# ElectroII.net
KiCad netlist of a schematic drawn in EAGLE
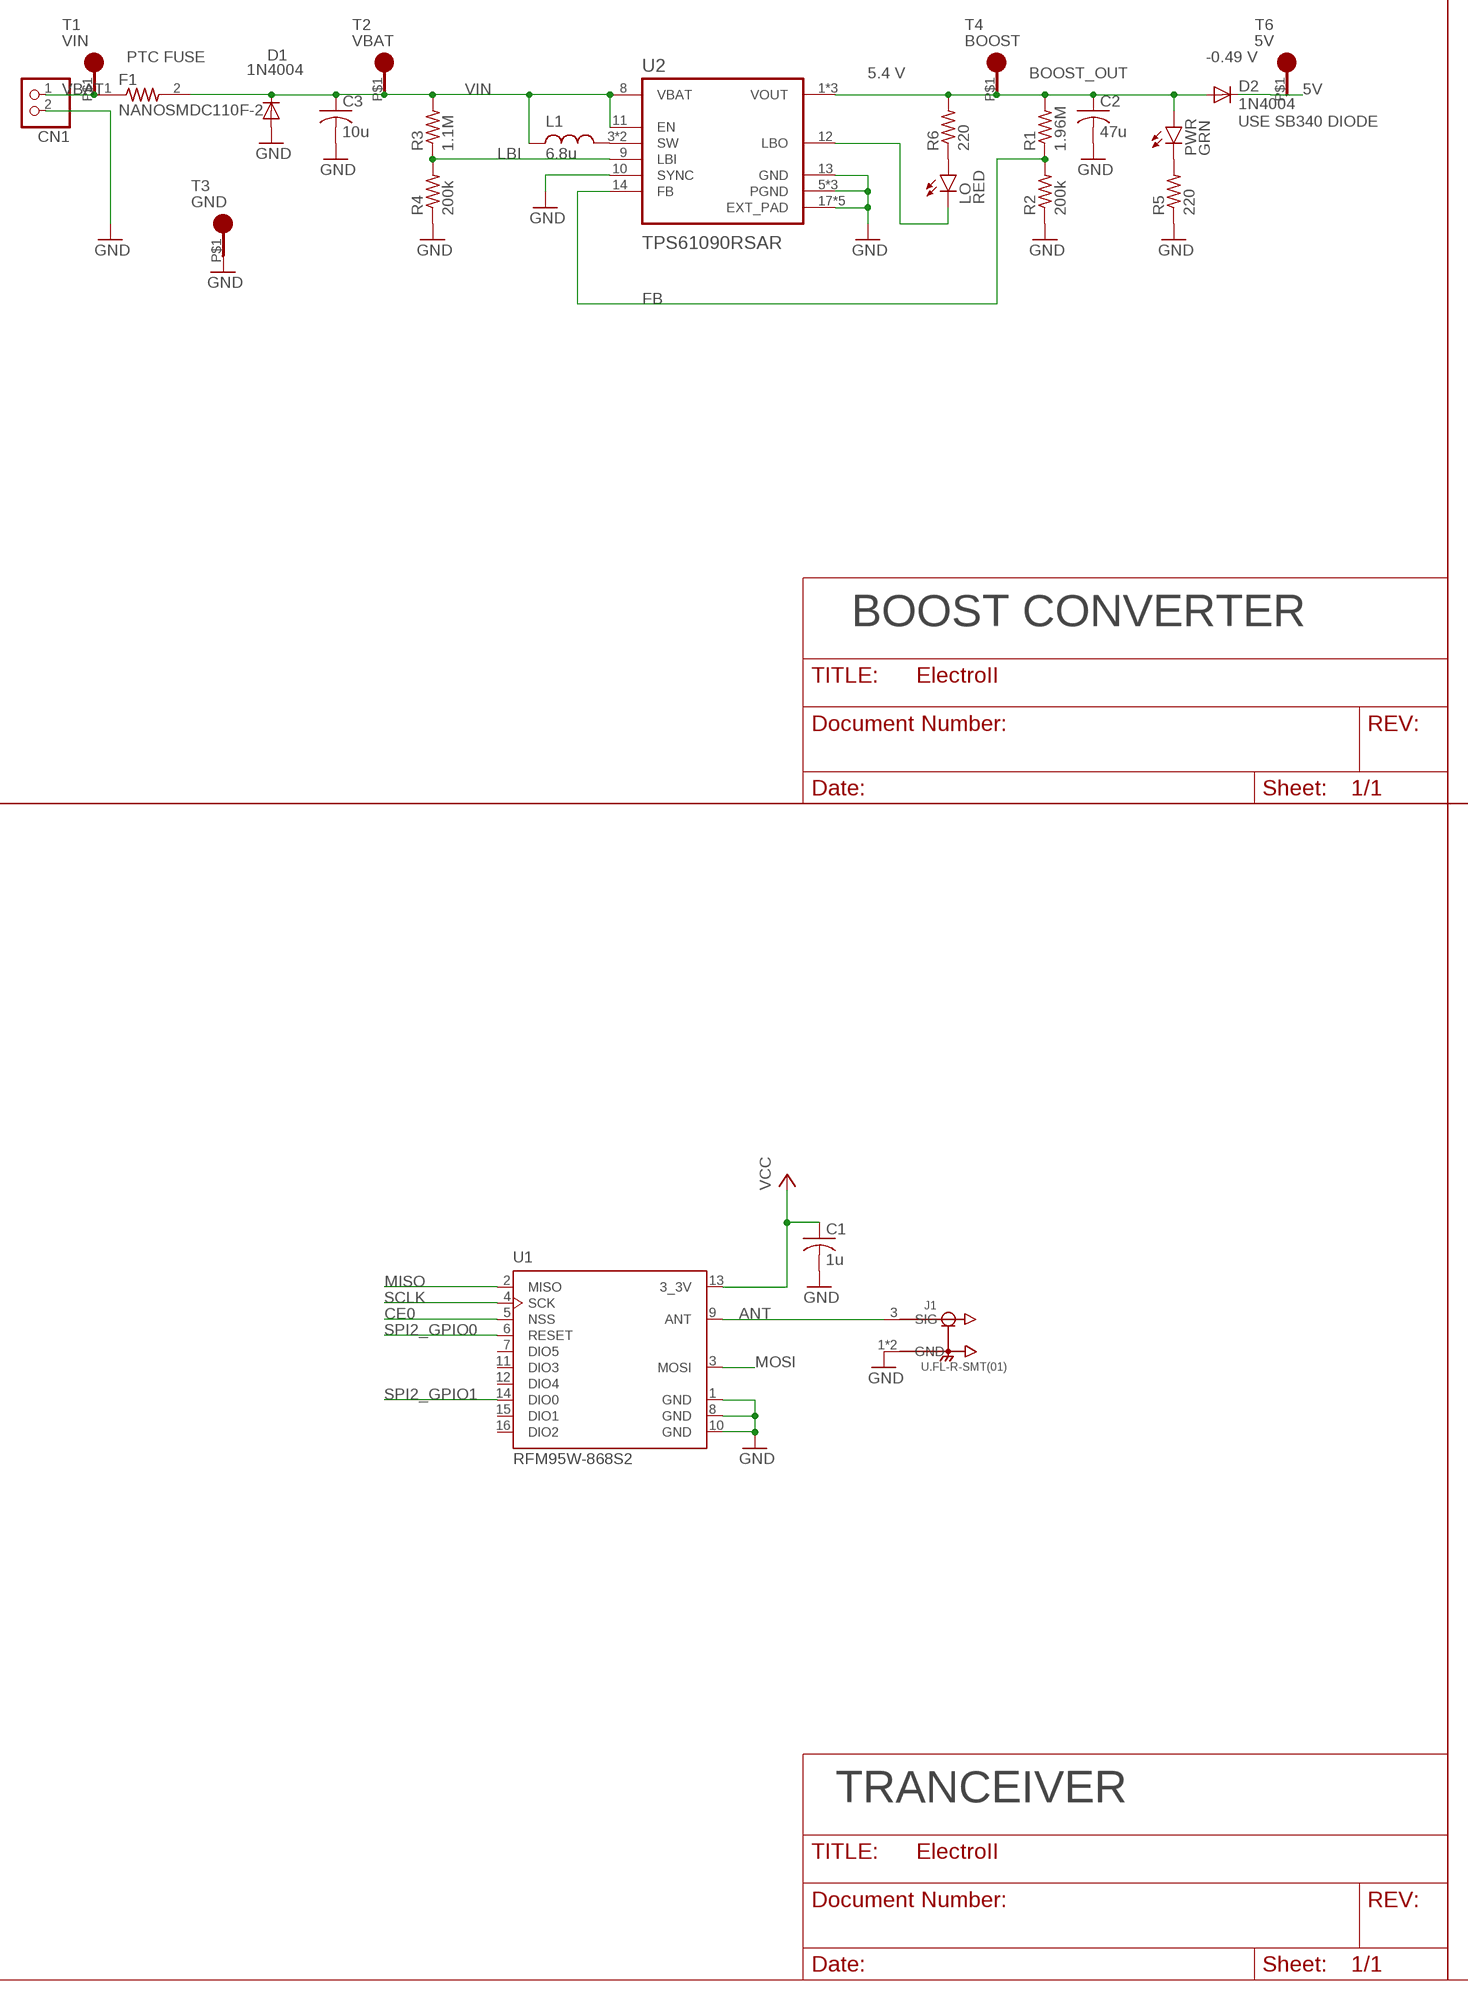
[diagram p0: schematic, sheet 1, part 1 of 2]
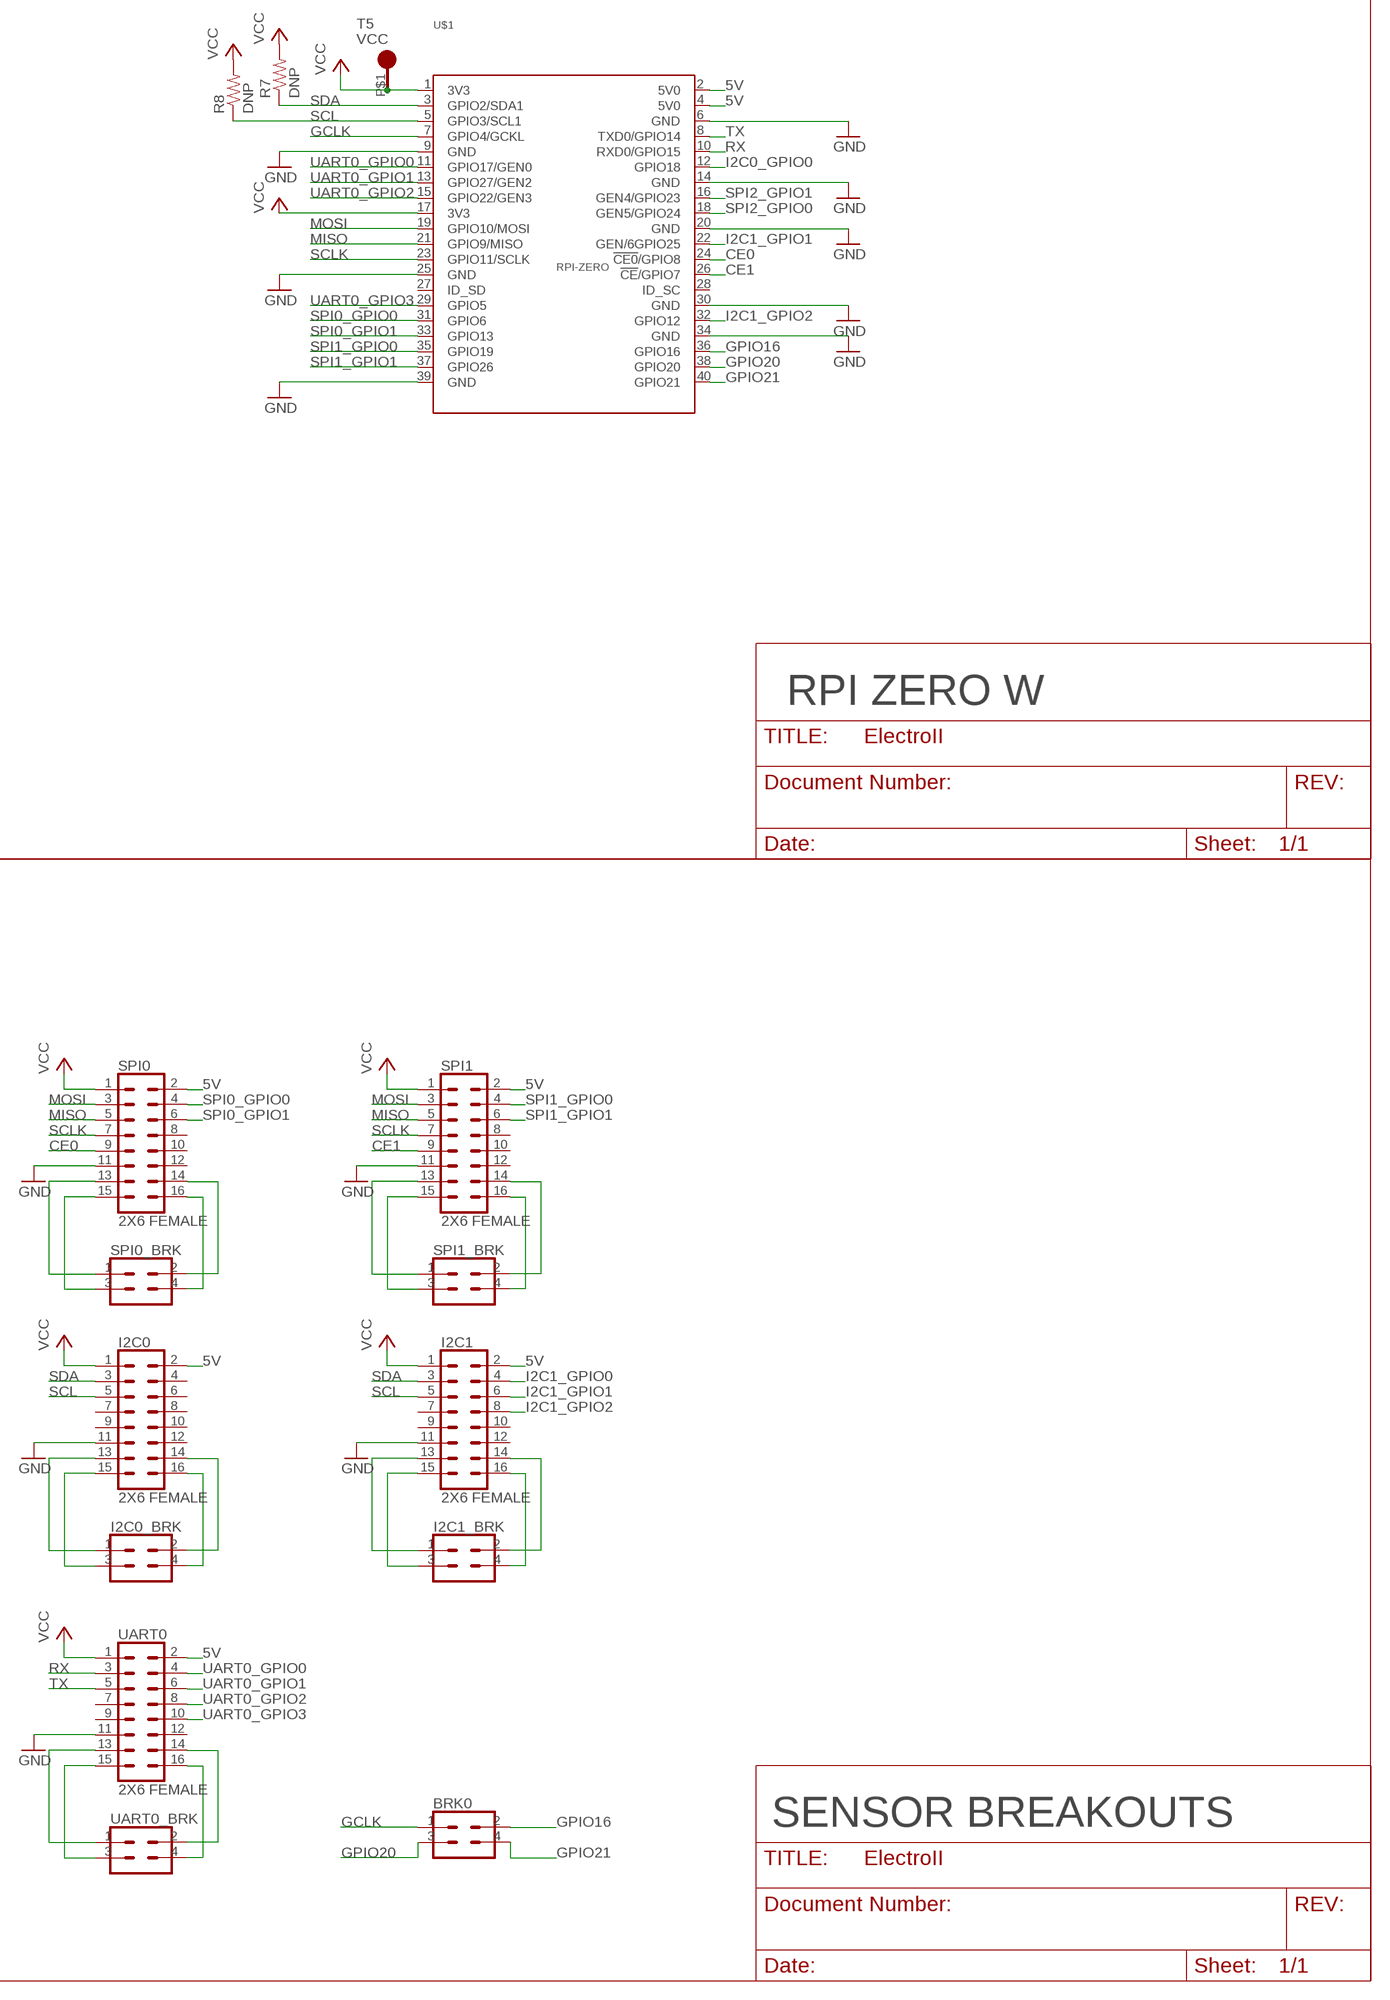
[diagram p1: schematic, sheet 1, part 2 of 2]

(export (version "E")
  (design (tool "Eeschema 10.0.6"))
  (components
    (comp (ref "BRK0")
      (value "SENSOR_PIN_BREAKOUT")
      (footprint "eagle-import:2X2")
      (libsource (lib "eagle-import") (part "SENSOR_PIN_BREAKOUT"))
    )
    (comp (ref "C1")
      (value "1u")
      (footprint "eagle-import:C1206")
      (libsource (lib "eagle-import") (part "C-ALL_PACKAGESC1206"))
    )
    (comp (ref "C2")
      (value "47u")
      (footprint "eagle-import:C1206")
      (libsource (lib "eagle-import") (part "C-ALL_PACKAGESC1206"))
    )
    (comp (ref "C3")
      (value "10u")
      (footprint "eagle-import:C1206")
      (libsource (lib "eagle-import") (part "C-ALL_PACKAGESC1206"))
    )
    (comp (ref "CN1")
      (value "JST_2PIN-SMT-RA")
      (footprint "eagle-import:JST-PH-2-SMT-RA")
      (libsource (lib "eagle-import") (part "JST_2PIN-SMT-RA"))
    )
    (comp (ref "D1")
      (value "1N4004")
      (footprint "eagle-import:DO41-10")
      (libsource (lib "eagle-import") (part "1N4004"))
    )
    (comp (ref "D2")
      (value "1N4004")
      (footprint "eagle-import:DO41-10")
      (libsource (lib "eagle-import") (part "1N4004"))
    )
    (comp (ref "F1")
      (value "NANOSMDC110F-2")
      (footprint "eagle-import:RESC3115X65N")
      (fields
        (field (name "DIGI-KEY_PART_NUMBER") "NANOSMDC110F-2CT-ND")
        (field (name "MF") "Littelfuse Inc.")
      )
      (libsource (lib "eagle-import") (part "NANOSMDC110F-2"))
    )
    (comp (ref "I2C0")
      (value "2X6 FEMALE")
      (footprint "eagle-import:2X7")
      (libsource (lib "eagle-import") (part "SENSOR_BREAKOUTPTH_FEMALE"))
    )
    (comp (ref "I2C0_BRK")
      (value "SENSOR_PIN_BREAKOUT")
      (footprint "eagle-import:2X2")
      (libsource (lib "eagle-import") (part "SENSOR_PIN_BREAKOUT"))
    )
    (comp (ref "I2C1")
      (value "2X6 FEMALE")
      (footprint "eagle-import:2X7")
      (libsource (lib "eagle-import") (part "SENSOR_BREAKOUTPTH_FEMALE"))
    )
    (comp (ref "I2C1_BRK")
      (value "SENSOR_PIN_BREAKOUT")
      (footprint "eagle-import:2X2")
      (libsource (lib "eagle-import") (part "SENSOR_PIN_BREAKOUT"))
    )
    (comp (ref "J1")
      (value "U.FL-R-SMT(01)")
      (footprint "eagle-import:HRS_U.FL-R-SMT(01)")
      (fields
        (field (name "DIGI-KEY_PART_NUMBER") "H9161-ND")
        (field (name "MF") "Hirose")
        (field (name "MP") "U.FL-R-SMT_01_")
      )
      (libsource (lib "eagle-import") (part "U.FL-R-SMT(01)"))
    )
    (comp (ref "L1")
      (value "6.8u")
      (footprint "eagle-import:L-DS75LC")
      (libsource (lib "eagle-import") (part "L_SMD"))
    )
    (comp (ref "LO")
      (value "RED")
      (footprint "eagle-import:LED5MM")
      (libsource (lib "eagle-import") (part "LED5MM"))
    )
    (comp (ref "PWR")
      (value "GRN")
      (footprint "eagle-import:LED5MM")
      (libsource (lib "eagle-import") (part "LED5MM"))
    )
    (comp (ref "R1")
      (value "1.96M")
      (footprint "eagle-import:R1206")
      (libsource (lib "eagle-import") (part "R-ALL_PACKAGESR1206"))
    )
    (comp (ref "R2")
      (value "200k")
      (footprint "eagle-import:R1206")
      (libsource (lib "eagle-import") (part "R-ALL_PACKAGESR1206"))
    )
    (comp (ref "R3")
      (value "1.1M")
      (footprint "eagle-import:R1206")
      (libsource (lib "eagle-import") (part "R-ALL_PACKAGESR1206"))
    )
    (comp (ref "R4")
      (value "200k")
      (footprint "eagle-import:R1206")
      (libsource (lib "eagle-import") (part "R-ALL_PACKAGESR1206"))
    )
    (comp (ref "R5")
      (value "220")
      (footprint "eagle-import:R1206")
      (libsource (lib "eagle-import") (part "R-ALL_PACKAGESR1206"))
    )
    (comp (ref "R6")
      (value "220")
      (footprint "eagle-import:R1206")
      (libsource (lib "eagle-import") (part "R-ALL_PACKAGESR1206"))
    )
    (comp (ref "R7")
      (value "DNP")
      (footprint "eagle-import:R1206")
      (libsource (lib "eagle-import") (part "R-ALL_PACKAGESR1206"))
    )
    (comp (ref "R8")
      (value "DNP")
      (footprint "eagle-import:R1206")
      (libsource (lib "eagle-import") (part "R-ALL_PACKAGESR1206"))
    )
    (comp (ref "SPI0")
      (value "2X6 FEMALE")
      (footprint "eagle-import:2X7")
      (libsource (lib "eagle-import") (part "SENSOR_BREAKOUTPTH_FEMALE"))
    )
    (comp (ref "SPI0_BRK")
      (value "SENSOR_PIN_BREAKOUT")
      (footprint "eagle-import:2X2")
      (libsource (lib "eagle-import") (part "SENSOR_PIN_BREAKOUT"))
    )
    (comp (ref "SPI1")
      (value "2X6 FEMALE")
      (footprint "eagle-import:2X7")
      (libsource (lib "eagle-import") (part "SENSOR_BREAKOUTPTH_FEMALE"))
    )
    (comp (ref "SPI1_BRK")
      (value "SENSOR_PIN_BREAKOUT")
      (footprint "eagle-import:2X2")
      (libsource (lib "eagle-import") (part "SENSOR_PIN_BREAKOUT"))
    )
    (comp (ref "T1")
      (value "VIN")
      (footprint "eagle-import:TEST_PAD")
      (libsource (lib "eagle-import") (part "TEST_PAD"))
    )
    (comp (ref "T2")
      (value "VBAT")
      (footprint "eagle-import:TEST_PAD")
      (libsource (lib "eagle-import") (part "TEST_PAD"))
    )
    (comp (ref "T3")
      (value "GND")
      (footprint "eagle-import:TEST_PAD")
      (libsource (lib "eagle-import") (part "TEST_PAD"))
    )
    (comp (ref "T4")
      (value "BOOST")
      (footprint "eagle-import:TEST_PAD")
      (libsource (lib "eagle-import") (part "TEST_PAD"))
    )
    (comp (ref "T5")
      (value "VCC")
      (footprint "eagle-import:TEST_PAD")
      (libsource (lib "eagle-import") (part "TEST_PAD"))
    )
    (comp (ref "T6")
      (value "5V")
      (footprint "eagle-import:TEST_PAD")
      (libsource (lib "eagle-import") (part "TEST_PAD"))
    )
    (comp (ref "U$1")
      (value "RPI-ZERO")
      (footprint "eagle-import:RASP_PI_ZERO_BOARD_FULL")
      (libsource (lib "eagle-import") (part "RPI-ZERO"))
    )
    (comp (ref "U1")
      (value "RFM95W-868S2")
      (footprint "eagle-import:XCVR_RFM95W-868S2")
      (fields (field (name "MF") "RF"))
      (libsource (lib "eagle-import") (part "RFM95W-868S2"))
    )
    (comp (ref "U2")
      (value "TPS61090RSAR")
      (footprint "eagle-import:QFN65P400X400X100-17N")
      (fields (field (name "DIGI-KEY_PART_NUMBER") "296-15259-1-ND") (field (name "MF") "Texas Instruments"))
      (libsource (lib "eagle-import") (part "TPS61090RSAR"))
    )
    (comp (ref "UART0")
      (value "2X6 FEMALE")
      (footprint "eagle-import:2X7")
      (libsource (lib "eagle-import") (part "SENSOR_BREAKOUTPTH_FEMALE"))
    )
    (comp (ref "UART0_BRK")
      (value "SENSOR_PIN_BREAKOUT")
      (footprint "eagle-import:2X2")
      (libsource (lib "eagle-import") (part "SENSOR_PIN_BREAKOUT"))
    )
  )
  (nets
    (net (code "1") (name "/5V") (class "Default")
      (node (ref "D2") (pin "C") (pinfunction "C_C") (pintype "passive"))
      (node (ref "I2C0") (pin "2") (pinfunction "2_2") (pintype "passive"))
      (node (ref "I2C1") (pin "2") (pinfunction "2_2") (pintype "passive"))
      (node (ref "SPI0") (pin "2") (pinfunction "2_2") (pintype "passive"))
      (node (ref "SPI1") (pin "2") (pinfunction "2_2") (pintype "passive"))
      (node (ref "T6") (pin "P$1") (pinfunction "P$1_P$1") (pintype "passive"))
      (node (ref "U$1") (pin "2") (pinfunction "5V0_2") (pintype "power_in"))
      (node (ref "U$1") (pin "4") (pinfunction "5V0_4") (pintype "power_in"))
      (node (ref "UART0") (pin "2") (pinfunction "2_2") (pintype "passive"))
    )
    (net (code "2") (name "/ANT") (class "Default")
      (node (ref "J1") (pin "3") (pinfunction "SIG_3") (pintype "passive"))
      (node (ref "U1") (pin "9") (pinfunction "ANT_9") (pintype "passive"))
    )
    (net (code "3") (name "/BOOST_OUT") (class "Default")
      (node (ref "C2") (pin "1") (pinfunction "1_1") (pintype "passive"))
      (node (ref "D2") (pin "A") (pinfunction "A_A") (pintype "passive"))
      (node (ref "PWR") (pin "A") (pinfunction "A_A") (pintype "passive"))
      (node (ref "R1") (pin "2") (pinfunction "2_2") (pintype "passive"))
      (node (ref "R6") (pin "2") (pinfunction "2_2") (pintype "passive"))
      (node (ref "T4") (pin "P$1") (pinfunction "P$1_P$1") (pintype "passive"))
      (node (ref "U2") (pin "1") (pinfunction "VOUT_1") (pintype "output"))
      (node (ref "U2") (pin "15") (pinfunction "VOUT_15") (pintype "output"))
      (node (ref "U2") (pin "16") (pinfunction "VOUT_16") (pintype "output"))
    )
    (net (code "4") (name "/CE0") (class "Default")
      (node (ref "SPI0") (pin "9") (pinfunction "9_9") (pintype "passive"))
      (node (ref "U$1") (pin "24") (pinfunction "~{CE0}/GPIO8_24") (pintype "bidirectional"))
      (node (ref "U1") (pin "5") (pinfunction "NSS_5") (pintype "input"))
    )
    (net (code "5") (name "/CE1") (class "Default")
      (node (ref "SPI1") (pin "9") (pinfunction "9_9") (pintype "passive"))
      (node (ref "U$1") (pin "26") (pinfunction "~{CE}/GPIO7_26") (pintype "bidirectional"))
    )
    (net (code "6") (name "/FB") (class "Default")
      (node (ref "R1") (pin "1") (pinfunction "1_1") (pintype "passive"))
      (node (ref "R2") (pin "2") (pinfunction "2_2") (pintype "passive"))
      (node (ref "U2") (pin "14") (pinfunction "FB_14") (pintype "input"))
    )
    (net (code "7") (name "/GCLK") (class "Default")
      (node (ref "BRK0") (pin "1") (pinfunction "1_1") (pintype "passive"))
      (node (ref "U$1") (pin "7") (pinfunction "GPIO4/GCKL_7") (pintype "bidirectional"))
    )
    (net (code "8") (name "/GPIO16") (class "Default")
      (node (ref "BRK0") (pin "2") (pinfunction "2_2") (pintype "passive"))
      (node (ref "U$1") (pin "36") (pinfunction "GPIO16_36") (pintype "bidirectional"))
    )
    (net (code "9") (name "/GPIO20") (class "Default")
      (node (ref "BRK0") (pin "3") (pinfunction "3_3") (pintype "passive"))
      (node (ref "U$1") (pin "38") (pinfunction "GPIO20_38") (pintype "bidirectional"))
    )
    (net (code "10") (name "/GPIO21") (class "Default")
      (node (ref "BRK0") (pin "4") (pinfunction "4_4") (pintype "passive"))
      (node (ref "U$1") (pin "40") (pinfunction "GPIO21_40") (pintype "bidirectional"))
    )
    (net (code "11") (name "/I2C0_GPIO0") (class "Default")
      (node (ref "U$1") (pin "12") (pinfunction "GPIO18_12") (pintype "bidirectional"))
    )
    (net (code "12") (name "/I2C1_GPIO0") (class "Default")
      (node (ref "I2C1") (pin "4") (pinfunction "4_4") (pintype "passive"))
    )
    (net (code "13") (name "/I2C1_GPIO1") (class "Default")
      (node (ref "I2C1") (pin "6") (pinfunction "6_6") (pintype "passive"))
      (node (ref "U$1") (pin "22") (pinfunction "GEN/6GPIO25_22") (pintype "bidirectional"))
    )
    (net (code "14") (name "/I2C1_GPIO2") (class "Default")
      (node (ref "I2C1") (pin "8") (pinfunction "8_8") (pintype "passive"))
      (node (ref "U$1") (pin "32") (pinfunction "GPIO12_32") (pintype "bidirectional"))
    )
    (net (code "15") (name "/LBI") (class "Default")
      (node (ref "R3") (pin "1") (pinfunction "1_1") (pintype "passive"))
      (node (ref "R4") (pin "2") (pinfunction "2_2") (pintype "passive"))
      (node (ref "U2") (pin "9") (pinfunction "LBI_9") (pintype "input"))
    )
    (net (code "16") (name "/MISO") (class "Default")
      (node (ref "SPI0") (pin "5") (pinfunction "5_5") (pintype "passive"))
      (node (ref "SPI1") (pin "5") (pinfunction "5_5") (pintype "passive"))
      (node (ref "U$1") (pin "21") (pinfunction "GPIO9/MISO_21") (pintype "bidirectional"))
      (node (ref "U1") (pin "2") (pinfunction "MISO_2") (pintype "input"))
    )
    (net (code "17") (name "/MOSI") (class "Default")
      (node (ref "SPI0") (pin "3") (pinfunction "3_3") (pintype "passive"))
      (node (ref "SPI1") (pin "3") (pinfunction "3_3") (pintype "passive"))
      (node (ref "U$1") (pin "19") (pinfunction "GPIO10/MOSI_19") (pintype "bidirectional"))
      (node (ref "U1") (pin "3") (pinfunction "MOSI_3") (pintype "output"))
    )
    (net (code "18") (name "/RX") (class "Default")
      (node (ref "U$1") (pin "10") (pinfunction "RXD0/GPIO15_10") (pintype "bidirectional"))
      (node (ref "UART0") (pin "3") (pinfunction "3_3") (pintype "passive"))
    )
    (net (code "19") (name "/SCL") (class "Default")
      (node (ref "I2C0") (pin "5") (pinfunction "5_5") (pintype "passive"))
      (node (ref "I2C1") (pin "5") (pinfunction "5_5") (pintype "passive"))
      (node (ref "R8") (pin "1") (pinfunction "1_1") (pintype "passive"))
      (node (ref "U$1") (pin "5") (pinfunction "GPIO3/SCL1_5") (pintype "bidirectional"))
    )
    (net (code "20") (name "/SCLK") (class "Default")
      (node (ref "SPI0") (pin "7") (pinfunction "7_7") (pintype "passive"))
      (node (ref "SPI1") (pin "7") (pinfunction "7_7") (pintype "passive"))
      (node (ref "U$1") (pin "23") (pinfunction "GPIO11/SCLK_23") (pintype "bidirectional"))
      (node (ref "U1") (pin "4") (pinfunction "SCK_4") (pintype "input"))
    )
    (net (code "21") (name "/SDA") (class "Default")
      (node (ref "I2C0") (pin "3") (pinfunction "3_3") (pintype "passive"))
      (node (ref "I2C1") (pin "3") (pinfunction "3_3") (pintype "passive"))
      (node (ref "R7") (pin "1") (pinfunction "1_1") (pintype "passive"))
      (node (ref "U$1") (pin "3") (pinfunction "GPIO2/SDA1_3") (pintype "bidirectional"))
    )
    (net (code "22") (name "/SPI0_GPIO0") (class "Default")
      (node (ref "SPI0") (pin "4") (pinfunction "4_4") (pintype "passive"))
      (node (ref "U$1") (pin "31") (pinfunction "GPIO6_31") (pintype "bidirectional"))
    )
    (net (code "23") (name "/SPI0_GPIO1") (class "Default")
      (node (ref "SPI0") (pin "6") (pinfunction "6_6") (pintype "passive"))
      (node (ref "U$1") (pin "33") (pinfunction "GPIO13_33") (pintype "bidirectional"))
    )
    (net (code "24") (name "/SPI1_GPIO0") (class "Default")
      (node (ref "SPI1") (pin "4") (pinfunction "4_4") (pintype "passive"))
      (node (ref "U$1") (pin "35") (pinfunction "GPIO19_35") (pintype "bidirectional"))
    )
    (net (code "25") (name "/SPI1_GPIO1") (class "Default")
      (node (ref "SPI1") (pin "6") (pinfunction "6_6") (pintype "passive"))
      (node (ref "U$1") (pin "37") (pinfunction "GPIO26_37") (pintype "bidirectional"))
    )
    (net (code "26") (name "/SPI2_GPIO0") (class "Default")
      (node (ref "U$1") (pin "18") (pinfunction "GEN5/GPIO24_18") (pintype "bidirectional"))
      (node (ref "U1") (pin "6") (pinfunction "RESET_6") (pintype "bidirectional"))
    )
    (net (code "27") (name "/SPI2_GPIO1") (class "Default")
      (node (ref "U$1") (pin "16") (pinfunction "GEN4/GPIO23_16") (pintype "bidirectional"))
      (node (ref "U1") (pin "14") (pinfunction "DIO0_14") (pintype "bidirectional"))
    )
    (net (code "28") (name "/TX") (class "Default")
      (node (ref "U$1") (pin "8") (pinfunction "TXD0/GPIO14_8") (pintype "bidirectional"))
      (node (ref "UART0") (pin "5") (pinfunction "5_5") (pintype "passive"))
    )
    (net (code "29") (name "/UART0_GPIO0") (class "Default")
      (node (ref "U$1") (pin "11") (pinfunction "GPIO17/GEN0_11") (pintype "bidirectional"))
      (node (ref "UART0") (pin "4") (pinfunction "4_4") (pintype "passive"))
    )
    (net (code "30") (name "/UART0_GPIO1") (class "Default")
      (node (ref "U$1") (pin "13") (pinfunction "GPIO27/GEN2_13") (pintype "bidirectional"))
      (node (ref "UART0") (pin "6") (pinfunction "6_6") (pintype "passive"))
    )
    (net (code "31") (name "/UART0_GPIO2") (class "Default")
      (node (ref "U$1") (pin "15") (pinfunction "GPIO22/GEN3_15") (pintype "bidirectional"))
      (node (ref "UART0") (pin "8") (pinfunction "8_8") (pintype "passive"))
    )
    (net (code "32") (name "/UART0_GPIO3") (class "Default")
      (node (ref "U$1") (pin "29") (pinfunction "GPIO5_29") (pintype "bidirectional"))
      (node (ref "UART0") (pin "10") (pinfunction "10_10") (pintype "passive"))
    )
    (net (code "33") (name "/VBAT") (class "Default")
      (node (ref "CN1") (pin "1") (pinfunction "2_1") (pintype "passive"))
      (node (ref "F1") (pin "1") (pinfunction "1_1") (pintype "passive"))
      (node (ref "T1") (pin "P$1") (pinfunction "P$1_P$1") (pintype "passive"))
    )
    (net (code "34") (name "/VIN") (class "Default")
      (node (ref "C3") (pin "1") (pinfunction "1_1") (pintype "passive"))
      (node (ref "D1") (pin "C") (pinfunction "C_C") (pintype "passive"))
      (node (ref "F1") (pin "2") (pinfunction "2_2") (pintype "passive"))
      (node (ref "L1") (pin "P$1") (pinfunction "1_P$1") (pintype "passive"))
      (node (ref "R3") (pin "2") (pinfunction "2_2") (pintype "passive"))
      (node (ref "T2") (pin "P$1") (pinfunction "P$1_P$1") (pintype "passive"))
      (node (ref "U2") (pin "11") (pinfunction "EN_11") (pintype "input"))
      (node (ref "U2") (pin "8") (pinfunction "VBAT_8") (pintype "input"))
    )
    (net (code "35") (name "GND") (class "Default")
      (node (ref "C1") (pin "2") (pinfunction "2_2") (pintype "passive"))
      (node (ref "C2") (pin "2") (pinfunction "2_2") (pintype "passive"))
      (node (ref "C3") (pin "2") (pinfunction "2_2") (pintype "passive"))
      (node (ref "CN1") (pin "2") (pinfunction "1_2") (pintype "passive"))
      (node (ref "D1") (pin "A") (pinfunction "A_A") (pintype "passive"))
      (node (ref "I2C0") (pin "11") (pinfunction "11_11") (pintype "passive"))
      (node (ref "I2C1") (pin "11") (pinfunction "11_11") (pintype "passive"))
      (node (ref "J1") (pin "1") (pinfunction "GND_1") (pintype "passive"))
      (node (ref "J1") (pin "2") (pinfunction "GND_2") (pintype "passive"))
      (node (ref "R2") (pin "1") (pinfunction "1_1") (pintype "passive"))
      (node (ref "R4") (pin "1") (pinfunction "1_1") (pintype "passive"))
      (node (ref "R5") (pin "1") (pinfunction "1_1") (pintype "passive"))
      (node (ref "SPI0") (pin "11") (pinfunction "11_11") (pintype "passive"))
      (node (ref "SPI1") (pin "11") (pinfunction "11_11") (pintype "passive"))
      (node (ref "T3") (pin "P$1") (pinfunction "P$1_P$1") (pintype "passive"))
      (node (ref "U$1") (pin "14") (pinfunction "GND_14") (pintype "power_in"))
      (node (ref "U$1") (pin "20") (pinfunction "GND_20") (pintype "power_in"))
      (node (ref "U$1") (pin "25") (pinfunction "GND_25") (pintype "power_in"))
      (node (ref "U$1") (pin "30") (pinfunction "GND_30") (pintype "power_in"))
      (node (ref "U$1") (pin "34") (pinfunction "GND_34") (pintype "power_in"))
      (node (ref "U$1") (pin "39") (pinfunction "GND_39") (pintype "power_in"))
      (node (ref "U$1") (pin "6") (pinfunction "GND_6") (pintype "power_in"))
      (node (ref "U$1") (pin "9") (pinfunction "GND_9") (pintype "power_in"))
      (node (ref "U1") (pin "1") (pinfunction "GND_1") (pintype "power_in"))
      (node (ref "U1") (pin "10") (pinfunction "GND_10") (pintype "power_in"))
      (node (ref "U1") (pin "8") (pinfunction "GND_8") (pintype "power_in"))
      (node (ref "U2") (pin "10") (pinfunction "SYNC_10") (pintype "input"))
      (node (ref "U2") (pin "13") (pinfunction "GND_13") (pintype "power_in"))
      (node (ref "U2") (pin "17") (pinfunction "EXT_PAD_17") (pintype "power_in"))
      (node (ref "U2") (pin "5") (pinfunction "PGND_5") (pintype "power_in"))
      (node (ref "U2") (pin "6") (pinfunction "PGND_6") (pintype "power_in"))
      (node (ref "U2") (pin "7") (pinfunction "PGND_7") (pintype "power_in"))
      (node (ref "U2") (pin "PGND1") (pinfunction "EXT_PAD_PGND1") (pintype "power_in"))
      (node (ref "U2") (pin "PGND2") (pinfunction "EXT_PAD_PGND2") (pintype "power_in"))
      (node (ref "U2") (pin "PGND3") (pinfunction "EXT_PAD_PGND3") (pintype "power_in"))
      (node (ref "U2") (pin "PGND4") (pinfunction "EXT_PAD_PGND4") (pintype "power_in"))
      (node (ref "UART0") (pin "11") (pinfunction "11_11") (pintype "passive"))
    )
    (net (code "36") (name "Net-(I2C0-Pad13)") (class "Default")
      (node (ref "I2C0") (pin "13") (pinfunction "13_13") (pintype "passive"))
      (node (ref "I2C0_BRK") (pin "1") (pinfunction "1_1") (pintype "passive"))
    )
    (net (code "37") (name "Net-(I2C0-Pad14)") (class "Default")
      (node (ref "I2C0") (pin "14") (pinfunction "14_14") (pintype "passive"))
      (node (ref "I2C0_BRK") (pin "2") (pinfunction "2_2") (pintype "passive"))
    )
    (net (code "38") (name "Net-(I2C0-Pad15)") (class "Default")
      (node (ref "I2C0") (pin "15") (pinfunction "15_15") (pintype "passive"))
      (node (ref "I2C0_BRK") (pin "3") (pinfunction "3_3") (pintype "passive"))
    )
    (net (code "39") (name "Net-(I2C0-Pad16)") (class "Default")
      (node (ref "I2C0") (pin "16") (pinfunction "16_16") (pintype "passive"))
      (node (ref "I2C0_BRK") (pin "4") (pinfunction "4_4") (pintype "passive"))
    )
    (net (code "40") (name "Net-(I2C1-Pad13)") (class "Default")
      (node (ref "I2C1") (pin "13") (pinfunction "13_13") (pintype "passive"))
      (node (ref "I2C1_BRK") (pin "1") (pinfunction "1_1") (pintype "passive"))
    )
    (net (code "41") (name "Net-(I2C1-Pad14)") (class "Default")
      (node (ref "I2C1") (pin "14") (pinfunction "14_14") (pintype "passive"))
      (node (ref "I2C1_BRK") (pin "2") (pinfunction "2_2") (pintype "passive"))
    )
    (net (code "42") (name "Net-(I2C1-Pad15)") (class "Default")
      (node (ref "I2C1") (pin "15") (pinfunction "15_15") (pintype "passive"))
      (node (ref "I2C1_BRK") (pin "3") (pinfunction "3_3") (pintype "passive"))
    )
    (net (code "43") (name "Net-(I2C1-Pad16)") (class "Default")
      (node (ref "I2C1") (pin "16") (pinfunction "16_16") (pintype "passive"))
      (node (ref "I2C1_BRK") (pin "4") (pinfunction "4_4") (pintype "passive"))
    )
    (net (code "44") (name "Net-(L1-2)") (class "Default")
      (node (ref "L1") (pin "P$2") (pinfunction "2_P$2") (pintype "passive"))
      (node (ref "U2") (pin "3") (pinfunction "SW_3") (pintype "input"))
      (node (ref "U2") (pin "4") (pinfunction "SW_4") (pintype "input"))
    )
    (net (code "45") (name "Net-(LO-C)") (class "Default")
      (node (ref "LO") (pin "K") (pinfunction "C_K") (pintype "passive"))
      (node (ref "U2") (pin "12") (pinfunction "LBO_12") (pintype "output"))
    )
    (net (code "46") (name "Net-(LO-PadA)") (class "Default")
      (node (ref "LO") (pin "A") (pinfunction "A_A") (pintype "passive"))
      (node (ref "R6") (pin "1") (pinfunction "1_1") (pintype "passive"))
    )
    (net (code "47") (name "Net-(PWR-C)") (class "Default")
      (node (ref "PWR") (pin "K") (pinfunction "C_K") (pintype "passive"))
      (node (ref "R5") (pin "2") (pinfunction "2_2") (pintype "passive"))
    )
    (net (code "48") (name "Net-(SPI0-Pad13)") (class "Default")
      (node (ref "SPI0") (pin "13") (pinfunction "13_13") (pintype "passive"))
      (node (ref "SPI0_BRK") (pin "1") (pinfunction "1_1") (pintype "passive"))
    )
    (net (code "49") (name "Net-(SPI0-Pad14)") (class "Default")
      (node (ref "SPI0") (pin "14") (pinfunction "14_14") (pintype "passive"))
      (node (ref "SPI0_BRK") (pin "2") (pinfunction "2_2") (pintype "passive"))
    )
    (net (code "50") (name "Net-(SPI0-Pad15)") (class "Default")
      (node (ref "SPI0") (pin "15") (pinfunction "15_15") (pintype "passive"))
      (node (ref "SPI0_BRK") (pin "3") (pinfunction "3_3") (pintype "passive"))
    )
    (net (code "51") (name "Net-(SPI0-Pad16)") (class "Default")
      (node (ref "SPI0") (pin "16") (pinfunction "16_16") (pintype "passive"))
      (node (ref "SPI0_BRK") (pin "4") (pinfunction "4_4") (pintype "passive"))
    )
    (net (code "52") (name "Net-(SPI1-Pad13)") (class "Default")
      (node (ref "SPI1") (pin "13") (pinfunction "13_13") (pintype "passive"))
      (node (ref "SPI1_BRK") (pin "1") (pinfunction "1_1") (pintype "passive"))
    )
    (net (code "53") (name "Net-(SPI1-Pad14)") (class "Default")
      (node (ref "SPI1") (pin "14") (pinfunction "14_14") (pintype "passive"))
      (node (ref "SPI1_BRK") (pin "2") (pinfunction "2_2") (pintype "passive"))
    )
    (net (code "54") (name "Net-(SPI1-Pad15)") (class "Default")
      (node (ref "SPI1") (pin "15") (pinfunction "15_15") (pintype "passive"))
      (node (ref "SPI1_BRK") (pin "3") (pinfunction "3_3") (pintype "passive"))
    )
    (net (code "55") (name "Net-(SPI1-Pad16)") (class "Default")
      (node (ref "SPI1") (pin "16") (pinfunction "16_16") (pintype "passive"))
      (node (ref "SPI1_BRK") (pin "4") (pinfunction "4_4") (pintype "passive"))
    )
    (net (code "56") (name "Net-(UART0-Pad13)") (class "Default")
      (node (ref "UART0") (pin "13") (pinfunction "13_13") (pintype "passive"))
      (node (ref "UART0_BRK") (pin "1") (pinfunction "1_1") (pintype "passive"))
    )
    (net (code "57") (name "Net-(UART0-Pad14)") (class "Default")
      (node (ref "UART0") (pin "14") (pinfunction "14_14") (pintype "passive"))
      (node (ref "UART0_BRK") (pin "2") (pinfunction "2_2") (pintype "passive"))
    )
    (net (code "58") (name "Net-(UART0-Pad15)") (class "Default")
      (node (ref "UART0") (pin "15") (pinfunction "15_15") (pintype "passive"))
      (node (ref "UART0_BRK") (pin "3") (pinfunction "3_3") (pintype "passive"))
    )
    (net (code "59") (name "Net-(UART0-Pad16)") (class "Default")
      (node (ref "UART0") (pin "16") (pinfunction "16_16") (pintype "passive"))
      (node (ref "UART0_BRK") (pin "4") (pinfunction "4_4") (pintype "passive"))
    )
    (net (code "60") (name "VCC") (class "Default")
      (node (ref "C1") (pin "1") (pinfunction "1_1") (pintype "passive"))
      (node (ref "I2C0") (pin "1") (pinfunction "1_1") (pintype "passive"))
      (node (ref "I2C1") (pin "1") (pinfunction "1_1") (pintype "passive"))
      (node (ref "R7") (pin "2") (pinfunction "2_2") (pintype "passive"))
      (node (ref "R8") (pin "2") (pinfunction "2_2") (pintype "passive"))
      (node (ref "SPI0") (pin "1") (pinfunction "1_1") (pintype "passive"))
      (node (ref "SPI1") (pin "1") (pinfunction "1_1") (pintype "passive"))
      (node (ref "T5") (pin "P$1") (pinfunction "P$1_P$1") (pintype "passive"))
      (node (ref "U$1") (pin "1") (pinfunction "3V3_1") (pintype "power_in"))
      (node (ref "U$1") (pin "17") (pinfunction "3V3_17") (pintype "power_in"))
      (node (ref "U1") (pin "13") (pinfunction "3_3V_13") (pintype "power_in"))
      (node (ref "UART0") (pin "1") (pinfunction "1_1") (pintype "passive"))
    )
    (net (code "61") (name "unconnected-(I2C0-Pad4)") (class "Default")
      (node (ref "I2C0") (pin "4") (pinfunction "4_4") (pintype "passive"))
    )
    (net (code "62") (name "unconnected-(I2C0-Pad6)") (class "Default")
      (node (ref "I2C0") (pin "6") (pinfunction "6_6") (pintype "passive"))
    )
    (net (code "63") (name "unconnected-(I2C0-Pad7)") (class "Default")
      (node (ref "I2C0") (pin "7") (pinfunction "7_7") (pintype "passive"))
    )
    (net (code "64") (name "unconnected-(I2C0-Pad8)") (class "Default")
      (node (ref "I2C0") (pin "8") (pinfunction "8_8") (pintype "passive"))
    )
    (net (code "65") (name "unconnected-(I2C0-Pad9)") (class "Default")
      (node (ref "I2C0") (pin "9") (pinfunction "9_9") (pintype "passive"))
    )
    (net (code "66") (name "unconnected-(I2C0-Pad10)") (class "Default")
      (node (ref "I2C0") (pin "10") (pinfunction "10_10") (pintype "passive"))
    )
    (net (code "67") (name "unconnected-(I2C0-Pad12)") (class "Default")
      (node (ref "I2C0") (pin "12") (pinfunction "12_12") (pintype "passive"))
    )
    (net (code "68") (name "unconnected-(I2C1-Pad7)") (class "Default")
      (node (ref "I2C1") (pin "7") (pinfunction "7_7") (pintype "passive"))
    )
    (net (code "69") (name "unconnected-(I2C1-Pad9)") (class "Default")
      (node (ref "I2C1") (pin "9") (pinfunction "9_9") (pintype "passive"))
    )
    (net (code "70") (name "unconnected-(I2C1-Pad10)") (class "Default")
      (node (ref "I2C1") (pin "10") (pinfunction "10_10") (pintype "passive"))
    )
    (net (code "71") (name "unconnected-(I2C1-Pad12)") (class "Default")
      (node (ref "I2C1") (pin "12") (pinfunction "12_12") (pintype "passive"))
    )
    (net (code "72") (name "unconnected-(SPI0-Pad8)") (class "Default")
      (node (ref "SPI0") (pin "8") (pinfunction "8_8") (pintype "passive"))
    )
    (net (code "73") (name "unconnected-(SPI0-Pad10)") (class "Default")
      (node (ref "SPI0") (pin "10") (pinfunction "10_10") (pintype "passive"))
    )
    (net (code "74") (name "unconnected-(SPI0-Pad12)") (class "Default")
      (node (ref "SPI0") (pin "12") (pinfunction "12_12") (pintype "passive"))
    )
    (net (code "75") (name "unconnected-(SPI1-Pad8)") (class "Default")
      (node (ref "SPI1") (pin "8") (pinfunction "8_8") (pintype "passive"))
    )
    (net (code "76") (name "unconnected-(SPI1-Pad10)") (class "Default")
      (node (ref "SPI1") (pin "10") (pinfunction "10_10") (pintype "passive"))
    )
    (net (code "77") (name "unconnected-(SPI1-Pad12)") (class "Default")
      (node (ref "SPI1") (pin "12") (pinfunction "12_12") (pintype "passive"))
    )
    (net (code "78") (name "unconnected-(U$1-ID_SC-Pad28)") (class "Default")
      (node (ref "U$1") (pin "28") (pinfunction "ID_SC_28") (pintype "bidirectional"))
    )
    (net (code "79") (name "unconnected-(U$1-ID_SD-Pad27)") (class "Default")
      (node (ref "U$1") (pin "27") (pinfunction "ID_SD_27") (pintype "bidirectional"))
    )
    (net (code "80") (name "unconnected-(U1-DIO1-Pad15)") (class "Default")
      (node (ref "U1") (pin "15") (pinfunction "DIO1_15") (pintype "bidirectional"))
    )
    (net (code "81") (name "unconnected-(U1-DIO2-Pad16)") (class "Default")
      (node (ref "U1") (pin "16") (pinfunction "DIO2_16") (pintype "bidirectional"))
    )
    (net (code "82") (name "unconnected-(U1-DIO3-Pad11)") (class "Default")
      (node (ref "U1") (pin "11") (pinfunction "DIO3_11") (pintype "bidirectional"))
    )
    (net (code "83") (name "unconnected-(U1-DIO4-Pad12)") (class "Default")
      (node (ref "U1") (pin "12") (pinfunction "DIO4_12") (pintype "bidirectional"))
    )
    (net (code "84") (name "unconnected-(U1-DIO5-Pad7)") (class "Default")
      (node (ref "U1") (pin "7") (pinfunction "DIO5_7") (pintype "bidirectional"))
    )
    (net (code "85") (name "unconnected-(UART0-Pad7)") (class "Default")
      (node (ref "UART0") (pin "7") (pinfunction "7_7") (pintype "passive"))
    )
    (net (code "86") (name "unconnected-(UART0-Pad9)") (class "Default")
      (node (ref "UART0") (pin "9") (pinfunction "9_9") (pintype "passive"))
    )
    (net (code "87") (name "unconnected-(UART0-Pad12)") (class "Default")
      (node (ref "UART0") (pin "12") (pinfunction "12_12") (pintype "passive"))
    )
  )
)
